# W5200_Ethernet_Shield.net
KiCad netlist of a schematic drawn in EAGLE
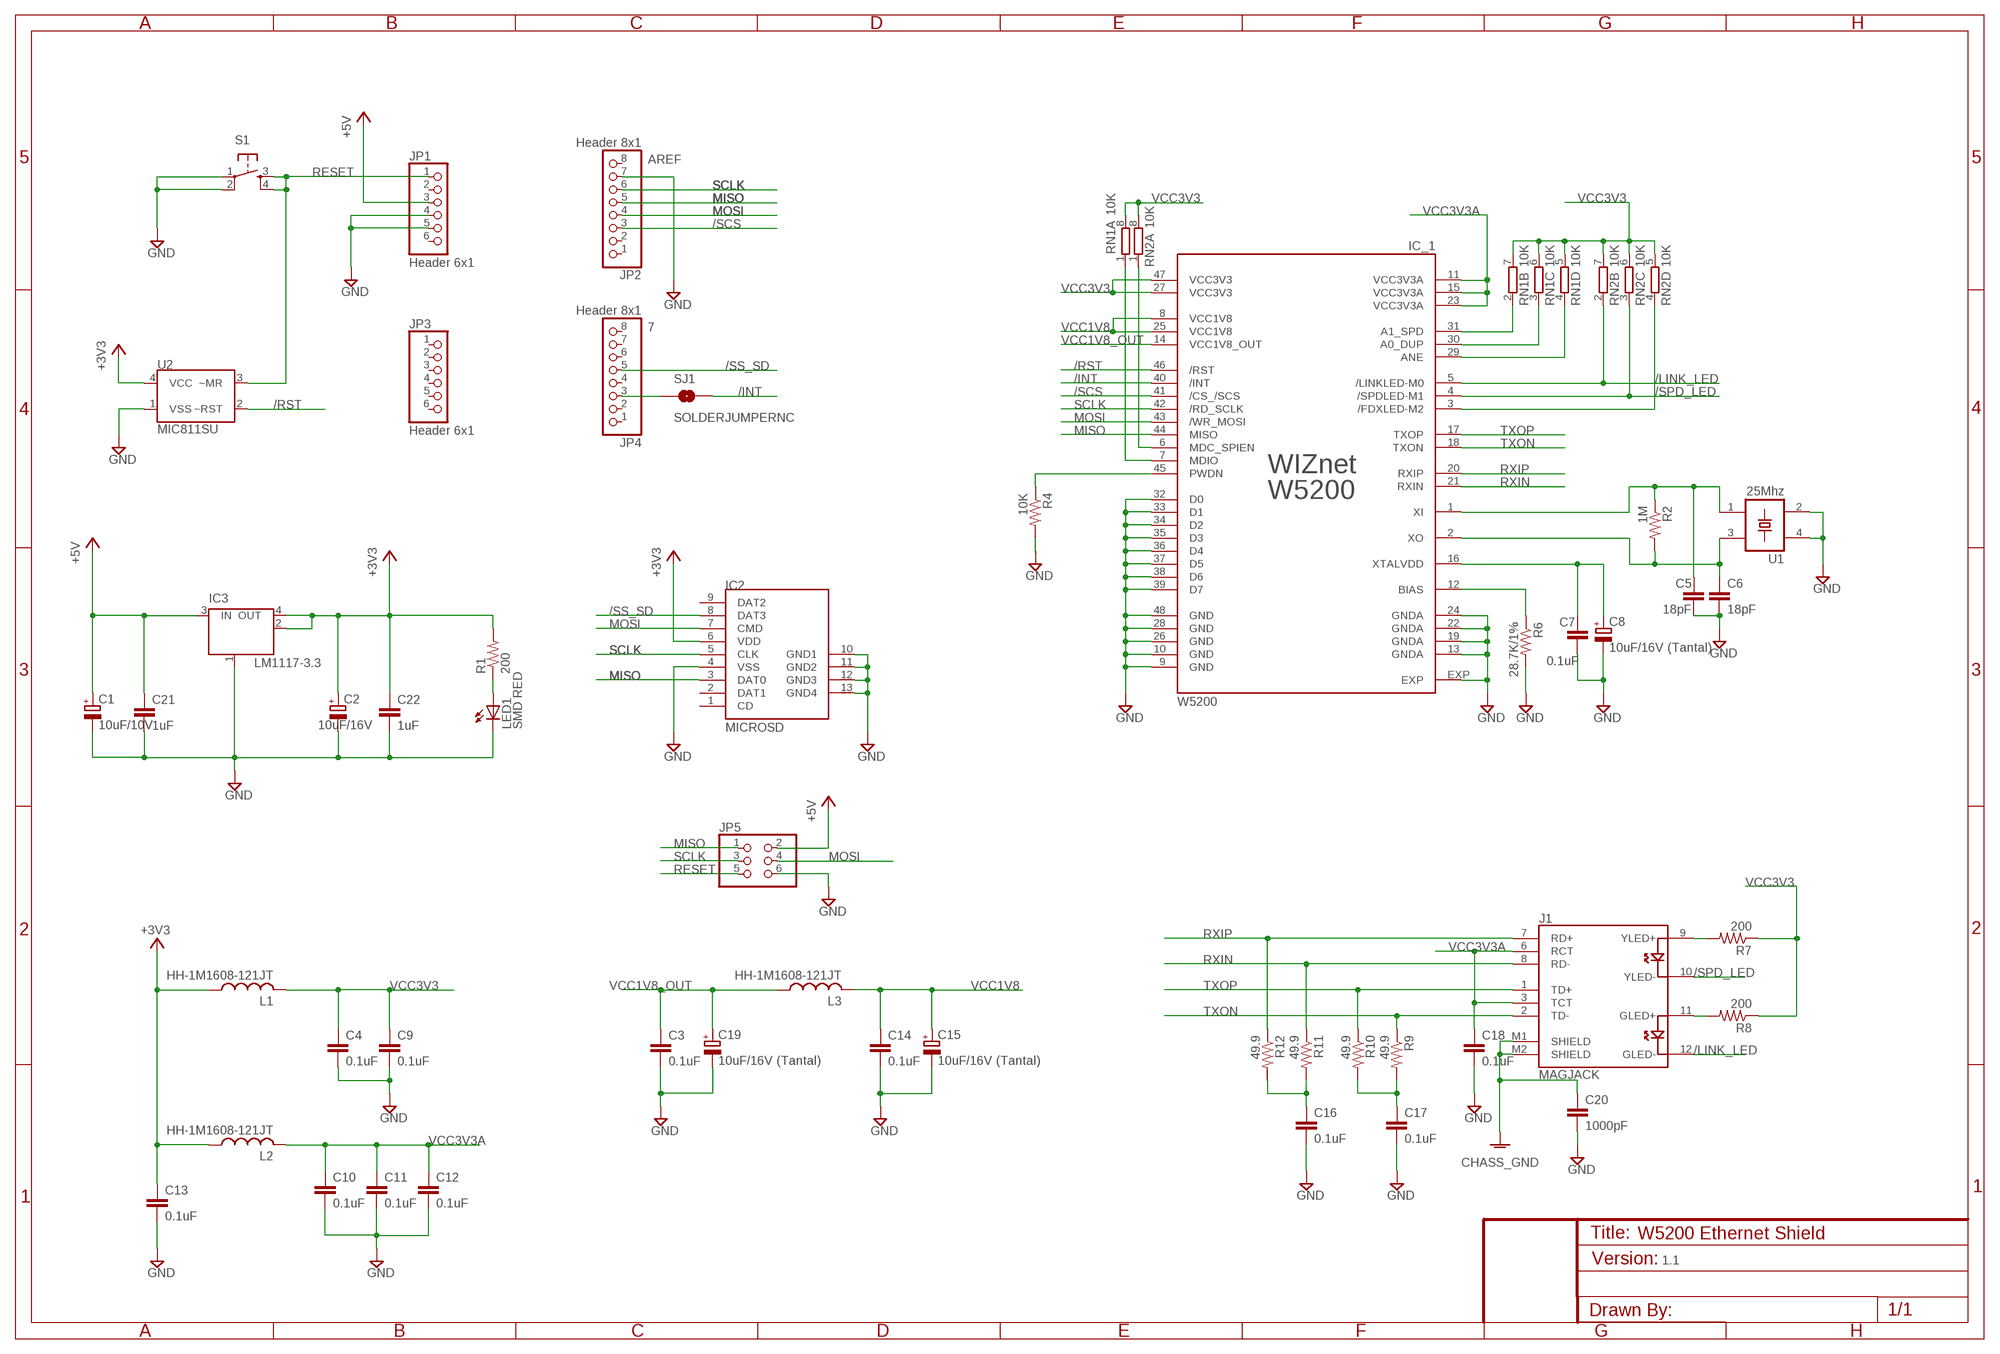
[diagram p0: schematic, sheet 1]

(export (version "E")
  (design (tool "Eeschema 10.0.6"))
  (components
    (comp (ref "C1")
      (value "10uF/10V")
      (footprint "eagle-import:CT3216")
      (libsource (lib "eagle-import") (part "CPOL-EUCT3216"))
    )
    (comp (ref "C2")
      (value "10uF/16V")
      (footprint "eagle-import:CT3216")
      (libsource (lib "eagle-import") (part "CPOL-EUCT3216"))
    )
    (comp (ref "C3")
      (value "0.1uF")
      (footprint "eagle-import:C0603")
      (libsource (lib "eagle-import") (part "C-EUC0603"))
    )
    (comp (ref "C4")
      (value "0.1uF")
      (footprint "eagle-import:C0603")
      (libsource (lib "eagle-import") (part "C-EUC0603"))
    )
    (comp (ref "C5")
      (value "18pF")
      (footprint "eagle-import:C0603")
      (libsource (lib "eagle-import") (part "C-EUC0603"))
    )
    (comp (ref "C6")
      (value "18pF")
      (footprint "eagle-import:C0603")
      (libsource (lib "eagle-import") (part "C-EUC0603"))
    )
    (comp (ref "C7")
      (value "0.1uF")
      (footprint "eagle-import:C0603")
      (libsource (lib "eagle-import") (part "C-EUC0603"))
    )
    (comp (ref "C8")
      (value "10uF/16V (Tantal)")
      (footprint "eagle-import:CT3216")
      (libsource (lib "eagle-import") (part "CPOL-EUCT3216"))
    )
    (comp (ref "C9")
      (value "0.1uF")
      (footprint "eagle-import:C0603")
      (libsource (lib "eagle-import") (part "C-EUC0603"))
    )
    (comp (ref "C10")
      (value "0.1uF")
      (footprint "eagle-import:C0603")
      (libsource (lib "eagle-import") (part "C-EUC0603"))
    )
    (comp (ref "C11")
      (value "0.1uF")
      (footprint "eagle-import:C0603")
      (libsource (lib "eagle-import") (part "C-EUC0603"))
    )
    (comp (ref "C12")
      (value "0.1uF")
      (footprint "eagle-import:C0603")
      (libsource (lib "eagle-import") (part "C-EUC0603"))
    )
    (comp (ref "C13")
      (value "0.1uF")
      (footprint "eagle-import:C0603")
      (libsource (lib "eagle-import") (part "C-EUC0603"))
    )
    (comp (ref "C14")
      (value "0.1uF")
      (footprint "eagle-import:C0603")
      (libsource (lib "eagle-import") (part "C-EUC0603"))
    )
    (comp (ref "C15")
      (value "10uF/16V (Tantal)")
      (footprint "eagle-import:CT3216")
      (libsource (lib "eagle-import") (part "CPOL-EUCT3216"))
    )
    (comp (ref "C16")
      (value "0.1uF")
      (footprint "eagle-import:C0603")
      (libsource (lib "eagle-import") (part "C-EUC0603"))
    )
    (comp (ref "C17")
      (value "0.1uF")
      (footprint "eagle-import:C0603")
      (libsource (lib "eagle-import") (part "C-EUC0603"))
    )
    (comp (ref "C18")
      (value "0.1uF")
      (footprint "eagle-import:C0603")
      (libsource (lib "eagle-import") (part "C-EUC0603"))
    )
    (comp (ref "C19")
      (value "10uF/16V (Tantal)")
      (footprint "eagle-import:CT3216")
      (libsource (lib "eagle-import") (part "CPOL-EUCT3216"))
    )
    (comp (ref "C20")
      (value "1000pF")
      (footprint "eagle-import:C3225")
      (libsource (lib "eagle-import") (part "C-EUC3225"))
    )
    (comp (ref "C21")
      (value "1uF")
      (footprint "eagle-import:C0603")
      (libsource (lib "eagle-import") (part "C-EUC0603"))
    )
    (comp (ref "C22")
      (value "1uF")
      (footprint "eagle-import:C0603")
      (libsource (lib "eagle-import") (part "C-EUC0603"))
    )
    (comp (ref "IC2")
      (value "MICROSD")
      (footprint "eagle-import:MSD_SYMBOL_MSDPAC")
      (libsource (lib "eagle-import") (part "MSD_SYMBOL_MICROSD"))
    )
    (comp (ref "IC3")
      (value "LM1117-3.3")
      (footprint "eagle-import:SOT223")
      (libsource (lib "eagle-import") (part "MC33269ST-3.3T3"))
    )
    (comp (ref "IC_1")
      (value "W5200")
      (footprint "eagle-import:QFN48")
      (libsource (lib "eagle-import") (part "W5200"))
    )
    (comp (ref "J1")
      (value "MAGJACK")
      (footprint "eagle-import:MAGJACK")
      (libsource (lib "eagle-import") (part "MAGJACK"))
    )
    (comp (ref "JP1")
      (value "Header 6x1")
      (footprint "eagle-import:1X06")
      (libsource (lib "eagle-import") (part "PINHD-1X6"))
    )
    (comp (ref "JP2")
      (value "Header 8x1")
      (footprint "eagle-import:1X08")
      (libsource (lib "eagle-import") (part "PINHD-1X8"))
    )
    (comp (ref "JP3")
      (value "Header 6x1")
      (footprint "eagle-import:1X06")
      (libsource (lib "eagle-import") (part "PINHD-1X6"))
    )
    (comp (ref "JP4")
      (value "Header 8x1")
      (footprint "eagle-import:1X08")
      (libsource (lib "eagle-import") (part "PINHD-1X8"))
    )
    (comp (ref "JP5")
      (value "PINHD-2X3")
      (footprint "eagle-import:2X03")
      (libsource (lib "eagle-import") (part "PINHD-2X3"))
    )
    (comp (ref "L1")
      (value "HH-1M1608-121JT")
      (footprint "eagle-import:L2012C")
      (libsource (lib "eagle-import") (part "L-USL2012C"))
    )
    (comp (ref "L2")
      (value "HH-1M1608-121JT")
      (footprint "eagle-import:L2012C")
      (libsource (lib "eagle-import") (part "L-USL2012C"))
    )
    (comp (ref "L3")
      (value "HH-1M1608-121JT")
      (footprint "eagle-import:L2012C")
      (libsource (lib "eagle-import") (part "L-USL2012C"))
    )
    (comp (ref "LED1")
      (value "SMD RED")
      (footprint "eagle-import:CHIP-LED0805")
      (libsource (lib "eagle-import") (part "LEDCHIP-LED0805"))
    )
    (comp (ref "R1")
      (value "200")
      (footprint "eagle-import:R0603")
      (libsource (lib "eagle-import") (part "R-US_R0603"))
    )
    (comp (ref "R2")
      (value "1M")
      (footprint "eagle-import:R0603")
      (libsource (lib "eagle-import") (part "R-US_R0603"))
    )
    (comp (ref "R4")
      (value "10K")
      (footprint "eagle-import:R0603")
      (libsource (lib "eagle-import") (part "R-US_R0603"))
    )
    (comp (ref "R6")
      (value "28.7K/1%")
      (footprint "eagle-import:R0603")
      (libsource (lib "eagle-import") (part "R-US_R0603"))
    )
    (comp (ref "R7")
      (value "200")
      (footprint "eagle-import:R0603")
      (libsource (lib "eagle-import") (part "R-US_R0603"))
    )
    (comp (ref "R8")
      (value "200")
      (footprint "eagle-import:R0603")
      (libsource (lib "eagle-import") (part "R-US_R0603"))
    )
    (comp (ref "R9")
      (value "49.9")
      (footprint "eagle-import:R0603")
      (libsource (lib "eagle-import") (part "R-US_R0603"))
    )
    (comp (ref "R10")
      (value "49.9")
      (footprint "eagle-import:R0603")
      (libsource (lib "eagle-import") (part "R-US_R0603"))
    )
    (comp (ref "R11")
      (value "49.9")
      (footprint "eagle-import:R0603")
      (libsource (lib "eagle-import") (part "R-US_R0603"))
    )
    (comp (ref "R12")
      (value "49.9")
      (footprint "eagle-import:R0603")
      (libsource (lib "eagle-import") (part "R-US_R0603"))
    )
    (comp (ref "RN1")
      (value "10K")
      (footprint "eagle-import:EXBV8V")
      (libsource (lib "eagle-import") (part "4R-NEXBV8V"))
    )
    (comp (ref "RN2")
      (value "10K")
      (footprint "eagle-import:EXBV8V")
      (libsource (lib "eagle-import") (part "4R-NEXBV8V"))
    )
    (comp (ref "S1")
      (value "TAC_SWITCHSMD")
      (footprint "eagle-import:TACTILE_SWITCH_SMD")
      (libsource (lib "eagle-import") (part "TAC_SWITCHSMD"))
    )
    (comp (ref "SJ1")
      (value "SOLDERJUMPERNC")
      (footprint "eagle-import:SJ_2S")
      (libsource (lib "eagle-import") (part "SOLDERJUMPERNC"))
    )
    (comp (ref "U1")
      (value "25Mhz")
      (footprint "eagle-import:CRYSTAL")
      (libsource (lib "eagle-import") (part "CRYSTAL"))
    )
    (comp (ref "U2")
      (value "MIC811SU")
      (footprint "eagle-import:SOT143")
      (libsource (lib "eagle-import") (part "STM811"))
    )
  )
  (nets
    (net (code "1") (name "+3V3") (class "Default")
      (node (ref "C13") (pin "1") (pinfunction "1_1") (pintype "passive"))
      (node (ref "C2") (pin "+") (pinfunction "+_+") (pintype "passive"))
      (node (ref "C22") (pin "1") (pinfunction "1_1") (pintype "passive"))
      (node (ref "IC2") (pin "6") (pinfunction "VDD_6") (pintype "bidirectional"))
      (node (ref "IC3") (pin "2") (pinfunction "OUT_2") (pintype "passive"))
      (node (ref "IC3") (pin "4") (pinfunction "OUT_4") (pintype "passive"))
      (node (ref "L1") (pin "1") (pinfunction "1_1") (pintype "passive"))
      (node (ref "L2") (pin "1") (pinfunction "1_1") (pintype "passive"))
      (node (ref "R1") (pin "2") (pinfunction "2_2") (pintype "passive"))
      (node (ref "U2") (pin "4") (pinfunction "VCC_4") (pintype "bidirectional"))
    )
    (net (code "2") (name "+5V") (class "Default")
      (node (ref "C1") (pin "+") (pinfunction "+_+") (pintype "passive"))
      (node (ref "C21") (pin "1") (pinfunction "1_1") (pintype "passive"))
      (node (ref "IC3") (pin "3") (pinfunction "IN_3") (pintype "input"))
      (node (ref "JP1") (pin "3") (pinfunction "3_3") (pintype "passive"))
      (node (ref "JP5") (pin "2") (pinfunction "2_2") (pintype "passive"))
    )
    (net (code "3") (name "/MISO") (class "Default")
      (node (ref "IC2") (pin "3") (pinfunction "DAT0_3") (pintype "bidirectional"))
      (node (ref "IC_1") (pin "44") (pinfunction "MISO_44") (pintype "bidirectional"))
      (node (ref "JP2") (pin "5") (pinfunction "5_5") (pintype "passive"))
      (node (ref "JP5") (pin "1") (pinfunction "1_1") (pintype "passive"))
    )
    (net (code "4") (name "/MOSI") (class "Default")
      (node (ref "IC2") (pin "7") (pinfunction "CMD_7") (pintype "bidirectional"))
      (node (ref "IC_1") (pin "43") (pinfunction "/WR_MOSI_43") (pintype "bidirectional"))
      (node (ref "JP2") (pin "4") (pinfunction "4_4") (pintype "passive"))
      (node (ref "JP5") (pin "4") (pinfunction "4_4") (pintype "passive"))
    )
    (net (code "5") (name "/RESET") (class "Default")
      (node (ref "JP1") (pin "1") (pinfunction "1_1") (pintype "passive"))
      (node (ref "JP5") (pin "5") (pinfunction "5_5") (pintype "passive"))
      (node (ref "S1") (pin "3") (pinfunction "3_3") (pintype "passive"))
      (node (ref "S1") (pin "4") (pinfunction "4_4") (pintype "passive"))
      (node (ref "U2") (pin "3") (pinfunction "~{MR}_3") (pintype "bidirectional"))
    )
    (net (code "6") (name "/RXIN") (class "Default")
      (node (ref "IC_1") (pin "21") (pinfunction "RXIN_21") (pintype "bidirectional"))
      (node (ref "J1") (pin "8") (pinfunction "RD-_8") (pintype "bidirectional"))
      (node (ref "R11") (pin "1") (pinfunction "1_1") (pintype "passive"))
    )
    (net (code "7") (name "/RXIP") (class "Default")
      (node (ref "IC_1") (pin "20") (pinfunction "RXIP_20") (pintype "bidirectional"))
      (node (ref "J1") (pin "7") (pinfunction "RD+_7") (pintype "bidirectional"))
      (node (ref "R12") (pin "1") (pinfunction "1_1") (pintype "passive"))
    )
    (net (code "8") (name "/SCLK") (class "Default")
      (node (ref "IC2") (pin "5") (pinfunction "CLK_5") (pintype "bidirectional"))
      (node (ref "IC_1") (pin "42") (pinfunction "/RD_SCLK_42") (pintype "bidirectional"))
      (node (ref "JP2") (pin "6") (pinfunction "6_6") (pintype "passive"))
      (node (ref "JP5") (pin "3") (pinfunction "3_3") (pintype "passive"))
    )
    (net (code "9") (name "/TXON") (class "Default")
      (node (ref "IC_1") (pin "18") (pinfunction "TXON_18") (pintype "bidirectional"))
      (node (ref "J1") (pin "2") (pinfunction "TD-_2") (pintype "bidirectional"))
      (node (ref "R9") (pin "1") (pinfunction "1_1") (pintype "passive"))
    )
    (net (code "10") (name "/TXOP") (class "Default")
      (node (ref "IC_1") (pin "17") (pinfunction "TXOP_17") (pintype "bidirectional"))
      (node (ref "J1") (pin "1") (pinfunction "TD+_1") (pintype "bidirectional"))
      (node (ref "R10") (pin "1") (pinfunction "1_1") (pintype "passive"))
    )
    (net (code "11") (name "/VCC1V8") (class "Default")
      (node (ref "C14") (pin "1") (pinfunction "1_1") (pintype "passive"))
      (node (ref "C15") (pin "+") (pinfunction "+_+") (pintype "passive"))
      (node (ref "IC_1") (pin "25") (pinfunction "VCC1V8_25") (pintype "bidirectional"))
      (node (ref "IC_1") (pin "8") (pinfunction "VCC1V8_8") (pintype "bidirectional"))
      (node (ref "L3") (pin "2") (pinfunction "2_2") (pintype "passive"))
    )
    (net (code "12") (name "/VCC1V8_OUT") (class "Default")
      (node (ref "C19") (pin "+") (pinfunction "+_+") (pintype "passive"))
      (node (ref "C3") (pin "1") (pinfunction "1_1") (pintype "passive"))
      (node (ref "IC_1") (pin "14") (pinfunction "VCC1V8_OUT_14") (pintype "bidirectional"))
      (node (ref "L3") (pin "1") (pinfunction "1_1") (pintype "passive"))
    )
    (net (code "13") (name "/VCC3V3") (class "Default")
      (node (ref "C4") (pin "1") (pinfunction "1_1") (pintype "passive"))
      (node (ref "C9") (pin "1") (pinfunction "1_1") (pintype "passive"))
      (node (ref "IC_1") (pin "27") (pinfunction "VCC3V3_27") (pintype "bidirectional"))
      (node (ref "IC_1") (pin "47") (pinfunction "VCC3V3_47") (pintype "bidirectional"))
      (node (ref "L1") (pin "2") (pinfunction "2_2") (pintype "passive"))
      (node (ref "R7") (pin "1") (pinfunction "1_1") (pintype "passive"))
      (node (ref "R8") (pin "1") (pinfunction "1_1") (pintype "passive"))
      (node (ref "RN1") (pin "5") (pinfunction "2_5") (pintype "passive"))
      (node (ref "RN1") (pin "6") (pinfunction "2_6") (pintype "passive"))
      (node (ref "RN1") (pin "7") (pinfunction "2_7") (pintype "passive"))
      (node (ref "RN1") (pin "8") (pinfunction "2_8") (pintype "passive"))
      (node (ref "RN2") (pin "5") (pinfunction "2_5") (pintype "passive"))
      (node (ref "RN2") (pin "6") (pinfunction "2_6") (pintype "passive"))
      (node (ref "RN2") (pin "7") (pinfunction "2_7") (pintype "passive"))
      (node (ref "RN2") (pin "8") (pinfunction "2_8") (pintype "passive"))
    )
    (net (code "14") (name "/VCC3V3A") (class "Default")
      (node (ref "C10") (pin "1") (pinfunction "1_1") (pintype "passive"))
      (node (ref "C11") (pin "1") (pinfunction "1_1") (pintype "passive"))
      (node (ref "C12") (pin "1") (pinfunction "1_1") (pintype "passive"))
      (node (ref "C18") (pin "1") (pinfunction "1_1") (pintype "passive"))
      (node (ref "IC_1") (pin "11") (pinfunction "VCC3V3A_11") (pintype "bidirectional"))
      (node (ref "IC_1") (pin "15") (pinfunction "VCC3V3A_15") (pintype "bidirectional"))
      (node (ref "IC_1") (pin "23") (pinfunction "VCC3V3A_23") (pintype "bidirectional"))
      (node (ref "J1") (pin "3") (pinfunction "TCT_3") (pintype "bidirectional"))
      (node (ref "J1") (pin "6") (pinfunction "RCT_6") (pintype "bidirectional"))
      (node (ref "L2") (pin "2") (pinfunction "2_2") (pintype "passive"))
    )
    (net (code "15") (name "/{slash}INT") (class "Default")
      (node (ref "IC_1") (pin "40") (pinfunction "/INT_40") (pintype "bidirectional"))
      (node (ref "SJ1") (pin "2") (pinfunction "2_2") (pintype "passive"))
    )
    (net (code "16") (name "/{slash}LINK_LED") (class "Default")
      (node (ref "IC_1") (pin "5") (pinfunction "/LINKLED-M0_5") (pintype "bidirectional"))
      (node (ref "J1") (pin "12") (pinfunction "GLED-_12") (pintype "bidirectional"))
      (node (ref "RN2") (pin "2") (pinfunction "1_2") (pintype "passive"))
    )
    (net (code "17") (name "/{slash}RST") (class "Default")
      (node (ref "IC_1") (pin "46") (pinfunction "/RST_46") (pintype "bidirectional"))
      (node (ref "U2") (pin "2") (pinfunction "~{RST}_2") (pintype "bidirectional"))
    )
    (net (code "18") (name "/{slash}SCS") (class "Default")
      (node (ref "IC_1") (pin "41") (pinfunction "/CS_/SCS_41") (pintype "bidirectional"))
      (node (ref "JP2") (pin "3") (pinfunction "3_3") (pintype "passive"))
    )
    (net (code "19") (name "/{slash}SPD_LED") (class "Default")
      (node (ref "IC_1") (pin "4") (pinfunction "/SPDLED-M1_4") (pintype "bidirectional"))
      (node (ref "J1") (pin "10") (pinfunction "YLED-_10") (pintype "bidirectional"))
      (node (ref "RN2") (pin "3") (pinfunction "1_3") (pintype "passive"))
    )
    (net (code "20") (name "/{slash}SS_SD") (class "Default")
      (node (ref "IC2") (pin "8") (pinfunction "DAT3_8") (pintype "bidirectional"))
      (node (ref "JP4") (pin "5") (pinfunction "5_5") (pintype "passive"))
    )
    (net (code "21") (name "CHASS_GND") (class "Default")
      (node (ref "C20") (pin "1") (pinfunction "1_1") (pintype "passive"))
      (node (ref "J1") (pin "M1") (pinfunction "SHIELD_M1") (pintype "bidirectional"))
      (node (ref "J1") (pin "M2") (pinfunction "SHIELD_M2") (pintype "bidirectional"))
    )
    (net (code "22") (name "GND") (class "Default")
      (node (ref "C1") (pin "-") (pinfunction "-_-") (pintype "passive"))
      (node (ref "C10") (pin "2") (pinfunction "2_2") (pintype "passive"))
      (node (ref "C11") (pin "2") (pinfunction "2_2") (pintype "passive"))
      (node (ref "C12") (pin "2") (pinfunction "2_2") (pintype "passive"))
      (node (ref "C13") (pin "2") (pinfunction "2_2") (pintype "passive"))
      (node (ref "C14") (pin "2") (pinfunction "2_2") (pintype "passive"))
      (node (ref "C15") (pin "-") (pinfunction "-_-") (pintype "passive"))
      (node (ref "C16") (pin "2") (pinfunction "2_2") (pintype "passive"))
      (node (ref "C17") (pin "2") (pinfunction "2_2") (pintype "passive"))
      (node (ref "C18") (pin "2") (pinfunction "2_2") (pintype "passive"))
      (node (ref "C19") (pin "-") (pinfunction "-_-") (pintype "passive"))
      (node (ref "C2") (pin "-") (pinfunction "-_-") (pintype "passive"))
      (node (ref "C20") (pin "2") (pinfunction "2_2") (pintype "passive"))
      (node (ref "C21") (pin "2") (pinfunction "2_2") (pintype "passive"))
      (node (ref "C22") (pin "2") (pinfunction "2_2") (pintype "passive"))
      (node (ref "C3") (pin "2") (pinfunction "2_2") (pintype "passive"))
      (node (ref "C4") (pin "2") (pinfunction "2_2") (pintype "passive"))
      (node (ref "C5") (pin "2") (pinfunction "2_2") (pintype "passive"))
      (node (ref "C6") (pin "2") (pinfunction "2_2") (pintype "passive"))
      (node (ref "C7") (pin "2") (pinfunction "2_2") (pintype "passive"))
      (node (ref "C8") (pin "-") (pinfunction "-_-") (pintype "passive"))
      (node (ref "C9") (pin "2") (pinfunction "2_2") (pintype "passive"))
      (node (ref "IC2") (pin "10") (pinfunction "GND1_10") (pintype "bidirectional"))
      (node (ref "IC2") (pin "11") (pinfunction "GND2_11") (pintype "bidirectional"))
      (node (ref "IC2") (pin "12") (pinfunction "GND3_12") (pintype "bidirectional"))
      (node (ref "IC2") (pin "13") (pinfunction "GND4_13") (pintype "bidirectional"))
      (node (ref "IC2") (pin "4") (pinfunction "VSS_4") (pintype "bidirectional"))
      (node (ref "IC3") (pin "1") (pinfunction "GND/ADJ_1") (pintype "input"))
      (node (ref "IC_1") (pin "10") (pinfunction "GND_10") (pintype "bidirectional"))
      (node (ref "IC_1") (pin "13") (pinfunction "GNDA_13") (pintype "bidirectional"))
      (node (ref "IC_1") (pin "19") (pinfunction "GNDA_19") (pintype "bidirectional"))
      (node (ref "IC_1") (pin "22") (pinfunction "GNDA_22") (pintype "bidirectional"))
      (node (ref "IC_1") (pin "24") (pinfunction "GNDA_24") (pintype "bidirectional"))
      (node (ref "IC_1") (pin "26") (pinfunction "GND_26") (pintype "bidirectional"))
      (node (ref "IC_1") (pin "28") (pinfunction "GND_28") (pintype "bidirectional"))
      (node (ref "IC_1") (pin "32") (pinfunction "D0_32") (pintype "bidirectional"))
      (node (ref "IC_1") (pin "33") (pinfunction "D1_33") (pintype "bidirectional"))
      (node (ref "IC_1") (pin "34") (pinfunction "D2_34") (pintype "bidirectional"))
      (node (ref "IC_1") (pin "35") (pinfunction "D3_35") (pintype "bidirectional"))
      (node (ref "IC_1") (pin "36") (pinfunction "D4_36") (pintype "bidirectional"))
      (node (ref "IC_1") (pin "37") (pinfunction "D5_37") (pintype "bidirectional"))
      (node (ref "IC_1") (pin "38") (pinfunction "D6_38") (pintype "bidirectional"))
      (node (ref "IC_1") (pin "39") (pinfunction "D7_39") (pintype "bidirectional"))
      (node (ref "IC_1") (pin "48") (pinfunction "GND_48") (pintype "bidirectional"))
      (node (ref "IC_1") (pin "9") (pinfunction "GND_9") (pintype "bidirectional"))
      (node (ref "IC_1") (pin "EXP") (pinfunction "EXP_EXP") (pintype "bidirectional"))
      (node (ref "JP1") (pin "4") (pinfunction "4_4") (pintype "passive"))
      (node (ref "JP1") (pin "5") (pinfunction "5_5") (pintype "passive"))
      (node (ref "JP2") (pin "7") (pinfunction "7_7") (pintype "passive"))
      (node (ref "JP5") (pin "6") (pinfunction "6_6") (pintype "passive"))
      (node (ref "LED1") (pin "C") (pinfunction "C_C") (pintype "passive"))
      (node (ref "R4") (pin "2") (pinfunction "2_2") (pintype "passive"))
      (node (ref "R6") (pin "2") (pinfunction "2_2") (pintype "passive"))
      (node (ref "S1") (pin "1") (pinfunction "1_1") (pintype "passive"))
      (node (ref "S1") (pin "2") (pinfunction "2_2") (pintype "passive"))
      (node (ref "U1") (pin "2") (pinfunction "GND0_2") (pintype "power_in"))
      (node (ref "U1") (pin "4") (pinfunction "GND1_4") (pintype "power_in"))
      (node (ref "U2") (pin "1") (pinfunction "VSS_1") (pintype "bidirectional"))
    )
    (net (code "23") (name "Net-(C16-Pad1)") (class "Default")
      (node (ref "C16") (pin "1") (pinfunction "1_1") (pintype "passive"))
      (node (ref "R11") (pin "2") (pinfunction "2_2") (pintype "passive"))
      (node (ref "R12") (pin "2") (pinfunction "2_2") (pintype "passive"))
    )
    (net (code "24") (name "Net-(C17-Pad1)") (class "Default")
      (node (ref "C17") (pin "1") (pinfunction "1_1") (pintype "passive"))
      (node (ref "R10") (pin "2") (pinfunction "2_2") (pintype "passive"))
      (node (ref "R9") (pin "2") (pinfunction "2_2") (pintype "passive"))
    )
    (net (code "25") (name "Net-(IC_1-A0_DUP)") (class "Default")
      (node (ref "IC_1") (pin "30") (pinfunction "A0_DUP_30") (pintype "bidirectional"))
      (node (ref "RN1") (pin "3") (pinfunction "1_3") (pintype "passive"))
    )
    (net (code "26") (name "Net-(IC_1-A1_SPD)") (class "Default")
      (node (ref "IC_1") (pin "31") (pinfunction "A1_SPD_31") (pintype "bidirectional"))
      (node (ref "RN1") (pin "2") (pinfunction "1_2") (pintype "passive"))
    )
    (net (code "27") (name "Net-(IC_1-ANE)") (class "Default")
      (node (ref "IC_1") (pin "29") (pinfunction "ANE_29") (pintype "bidirectional"))
      (node (ref "RN1") (pin "4") (pinfunction "1_4") (pintype "passive"))
    )
    (net (code "28") (name "Net-(IC_1-BIAS)") (class "Default")
      (node (ref "IC_1") (pin "12") (pinfunction "BIAS_12") (pintype "bidirectional"))
      (node (ref "R6") (pin "1") (pinfunction "1_1") (pintype "passive"))
    )
    (net (code "29") (name "Net-(IC_1-MDC_SPIEN)") (class "Default")
      (node (ref "IC_1") (pin "6") (pinfunction "MDC_SPIEN_6") (pintype "bidirectional"))
      (node (ref "RN2") (pin "1") (pinfunction "1_1") (pintype "passive"))
    )
    (net (code "30") (name "Net-(IC_1-MDIO)") (class "Default")
      (node (ref "IC_1") (pin "7") (pinfunction "MDIO_7") (pintype "bidirectional"))
      (node (ref "RN1") (pin "1") (pinfunction "1_1") (pintype "passive"))
    )
    (net (code "31") (name "Net-(IC_1-PWDN)") (class "Default")
      (node (ref "IC_1") (pin "45") (pinfunction "PWDN_45") (pintype "bidirectional"))
      (node (ref "R4") (pin "1") (pinfunction "1_1") (pintype "passive"))
    )
    (net (code "32") (name "Net-(IC_1-XI)") (class "Default")
      (node (ref "C5") (pin "1") (pinfunction "1_1") (pintype "passive"))
      (node (ref "IC_1") (pin "1") (pinfunction "XI_1") (pintype "bidirectional"))
      (node (ref "R2") (pin "1") (pinfunction "1_1") (pintype "passive"))
      (node (ref "U1") (pin "1") (pinfunction "TRI_1") (pintype "input"))
    )
    (net (code "33") (name "Net-(IC_1-XO)") (class "Default")
      (node (ref "C6") (pin "1") (pinfunction "1_1") (pintype "passive"))
      (node (ref "IC_1") (pin "2") (pinfunction "XO_2") (pintype "bidirectional"))
      (node (ref "R2") (pin "2") (pinfunction "2_2") (pintype "passive"))
      (node (ref "U1") (pin "3") (pinfunction "OUT_3") (pintype "output"))
    )
    (net (code "34") (name "Net-(IC_1-XTALVDD)") (class "Default")
      (node (ref "C7") (pin "1") (pinfunction "1_1") (pintype "passive"))
      (node (ref "C8") (pin "+") (pinfunction "+_+") (pintype "passive"))
      (node (ref "IC_1") (pin "16") (pinfunction "XTALVDD_16") (pintype "bidirectional"))
    )
    (net (code "35") (name "Net-(IC_1-{slash}FDXLED-M2)") (class "Default")
      (node (ref "IC_1") (pin "3") (pinfunction "/FDXLED-M2_3") (pintype "bidirectional"))
      (node (ref "RN2") (pin "4") (pinfunction "1_4") (pintype "passive"))
    )
    (net (code "36") (name "Net-(J1-GLED+)") (class "Default")
      (node (ref "J1") (pin "11") (pinfunction "GLED+_11") (pintype "bidirectional"))
      (node (ref "R8") (pin "2") (pinfunction "2_2") (pintype "passive"))
    )
    (net (code "37") (name "Net-(J1-YLED+)") (class "Default")
      (node (ref "J1") (pin "9") (pinfunction "YLED+_9") (pintype "bidirectional"))
      (node (ref "R7") (pin "2") (pinfunction "2_2") (pintype "passive"))
    )
    (net (code "38") (name "Net-(JP4-Pad3)") (class "Default")
      (node (ref "JP4") (pin "3") (pinfunction "3_3") (pintype "passive"))
      (node (ref "SJ1") (pin "1") (pinfunction "1_1") (pintype "passive"))
    )
    (net (code "39") (name "Net-(LED1-PadA)") (class "Default")
      (node (ref "LED1") (pin "A") (pinfunction "A_A") (pintype "passive"))
      (node (ref "R1") (pin "1") (pinfunction "1_1") (pintype "passive"))
    )
    (net (code "40") (name "unconnected-(IC2-CD-Pad1)") (class "Default")
      (node (ref "IC2") (pin "1") (pinfunction "CD_1") (pintype "bidirectional"))
    )
    (net (code "41") (name "unconnected-(IC2-DAT1-Pad2)") (class "Default")
      (node (ref "IC2") (pin "2") (pinfunction "DAT1_2") (pintype "bidirectional"))
    )
    (net (code "42") (name "unconnected-(IC2-DAT2-Pad9)") (class "Default")
      (node (ref "IC2") (pin "9") (pinfunction "DAT2_9") (pintype "bidirectional"))
    )
    (net (code "43") (name "unconnected-(JP1-Pad2)") (class "Default")
      (node (ref "JP1") (pin "2") (pinfunction "2_2") (pintype "passive"))
    )
    (net (code "44") (name "unconnected-(JP1-Pad6)") (class "Default")
      (node (ref "JP1") (pin "6") (pinfunction "6_6") (pintype "passive"))
    )
    (net (code "45") (name "unconnected-(JP2-Pad1)") (class "Default")
      (node (ref "JP2") (pin "1") (pinfunction "1_1") (pintype "passive"))
    )
    (net (code "46") (name "unconnected-(JP2-Pad2)") (class "Default")
      (node (ref "JP2") (pin "2") (pinfunction "2_2") (pintype "passive"))
    )
    (net (code "47") (name "unconnected-(JP2-Pad8)") (class "Default")
      (node (ref "JP2") (pin "8") (pinfunction "8_8") (pintype "passive"))
    )
    (net (code "48") (name "unconnected-(JP3-Pad1)") (class "Default")
      (node (ref "JP3") (pin "1") (pinfunction "1_1") (pintype "passive"))
    )
    (net (code "49") (name "unconnected-(JP3-Pad2)") (class "Default")
      (node (ref "JP3") (pin "2") (pinfunction "2_2") (pintype "passive"))
    )
    (net (code "50") (name "unconnected-(JP3-Pad3)") (class "Default")
      (node (ref "JP3") (pin "3") (pinfunction "3_3") (pintype "passive"))
    )
    (net (code "51") (name "unconnected-(JP3-Pad4)") (class "Default")
      (node (ref "JP3") (pin "4") (pinfunction "4_4") (pintype "passive"))
    )
    (net (code "52") (name "unconnected-(JP3-Pad5)") (class "Default")
      (node (ref "JP3") (pin "5") (pinfunction "5_5") (pintype "passive"))
    )
    (net (code "53") (name "unconnected-(JP3-Pad6)") (class "Default")
      (node (ref "JP3") (pin "6") (pinfunction "6_6") (pintype "passive"))
    )
    (net (code "54") (name "unconnected-(JP4-Pad1)") (class "Default")
      (node (ref "JP4") (pin "1") (pinfunction "1_1") (pintype "passive"))
    )
    (net (code "55") (name "unconnected-(JP4-Pad2)") (class "Default")
      (node (ref "JP4") (pin "2") (pinfunction "2_2") (pintype "passive"))
    )
    (net (code "56") (name "unconnected-(JP4-Pad4)") (class "Default")
      (node (ref "JP4") (pin "4") (pinfunction "4_4") (pintype "passive"))
    )
    (net (code "57") (name "unconnected-(JP4-Pad6)") (class "Default")
      (node (ref "JP4") (pin "6") (pinfunction "6_6") (pintype "passive"))
    )
    (net (code "58") (name "unconnected-(JP4-Pad7)") (class "Default")
      (node (ref "JP4") (pin "7") (pinfunction "7_7") (pintype "passive"))
    )
    (net (code "59") (name "unconnected-(JP4-Pad8)") (class "Default")
      (node (ref "JP4") (pin "8") (pinfunction "8_8") (pintype "passive"))
    )
  )
)
